# Sheet3.net
KiCad netlist of a schematic drawn in Altium Designer
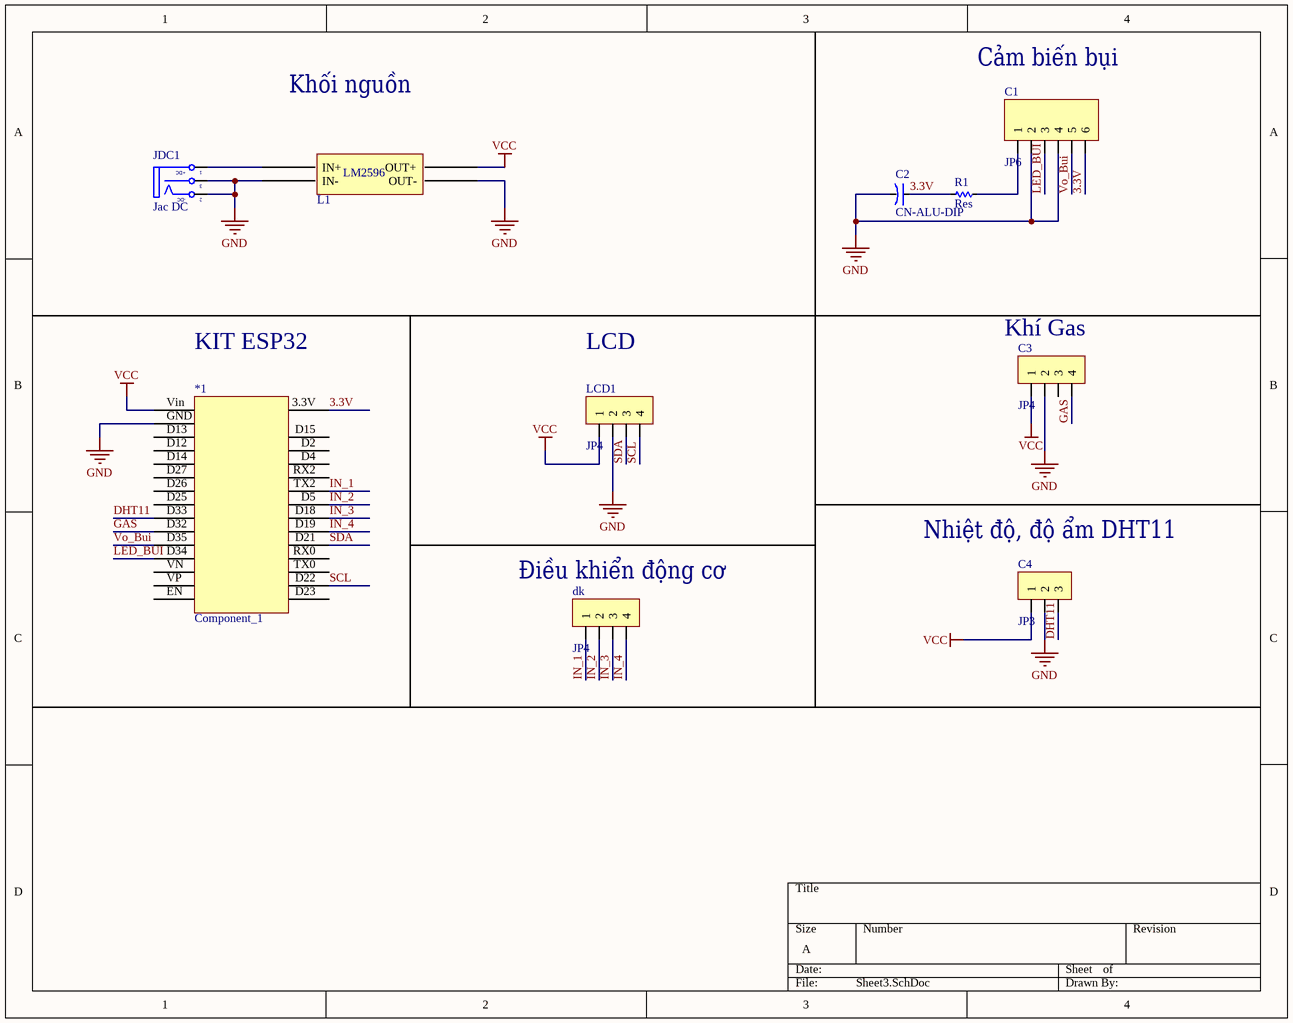
[diagram p0: Sheet3.SchDoc]

(export (version "E")
  (design (tool "Eeschema 10.0.6"))
  (components
    (comp (ref "*1")
      (value "Component_1")
      (footprint "PCBComponent_1")
      (libsource (lib "Schlib1") (part "Component_1"))
    )
    (comp (ref "C1")
      (value "JP6")
      (footprint "JP6-C1T")
      (description "WR-PHD 2.54 mm Angled Socket Header")
      (fields
        (field (name "MANUFACTURER") "Würth Elektronik eiSos GmbH")
        (field (name "PARTNO") "613006143121")
        (field (name "CREATED BY") "Karrer Zheng")
      )
      (libsource (lib "LIBRARY") (part "JP6"))
    )
    (comp (ref "C2")
      (value "CN-ALU-DIP")
      (footprint "CA-ALU-2.54")
      (description "Capacitor (Semiconductor SIM Model)")
      (fields (field (name "PUBLISHER") "Altium Limited"))
      (libsource (lib "LIBRARY") (part "CN-ALU-DIP"))
    )
    (comp (ref "C3")
      (value "JP4")
      (footprint "JP4-C1T")
      (description "WR-PHD 2.54 mm Angled Socket Header")
      (fields
        (field (name "MANUFACTURER") "Würth Elektronik eiSos GmbH")
        (field (name "PARTNO") "613004143121")
        (field (name "CREATED BY") "Karrer Zheng")
      )
      (libsource (lib "LIBRARY") (part "JP4"))
    )
    (comp (ref "C4")
      (value "JP3")
      (footprint "JP3-C1T")
      (description "WR-PHD 2.54 mm Angled Socket Header")
      (fields
        (field (name "MANUFACTURER") "Würth Elektronik eiSos GmbH")
        (field (name "PARTNO") "613003143121")
        (field (name "CREATED BY") "Karrer Zheng")
      )
      (libsource (lib "LIBRARY") (part "JP3"))
    )
    (comp (ref "dk")
      (value "JP4")
      (footprint "JP4-C1T")
      (description "WR-PHD 2.54 mm Angled Socket Header")
      (fields
        (field (name "MANUFACTURER") "Würth Elektronik eiSos GmbH")
        (field (name "PARTNO") "613004143121")
        (field (name "CREATED BY") "Karrer Zheng")
      )
      (libsource (lib "LIBRARY") (part "JP4"))
    )
    (comp (ref "JDC1")
      (value "Jac DC")
      (footprint "DC0")
      (description "Jac DC input")
      (libsource (lib "LIBRARY") (part "DCIN"))
    )
    (comp (ref "L1")
      (value "BUCK_LM2596")
      (footprint "BUCK_LM2596")
      (libsource (lib "BUCK_LM2596_Sch") (part "BUCK_LM2596"))
    )
    (comp (ref "LCD1")
      (value "JP4")
      (footprint "JP4-C1T")
      (description "WR-PHD 2.54 mm Angled Socket Header")
      (fields
        (field (name "MANUFACTURER") "Würth Elektronik eiSos GmbH")
        (field (name "PARTNO") "613004143121")
        (field (name "CREATED BY") "Karrer Zheng")
      )
      (libsource (lib "LIBRARY") (part "JP4"))
    )
    (comp (ref "R1")
      (value "Res")
      (footprint "RES-1/2W")
      (fields
        (field (name "MANUFACTURER") "Generic Components")
        (field (name "PUBLISHER") "Altium Hobart Technology Centre")
      )
      (libsource (lib "LIBRARY") (part "Res"))
    )
  )
  (nets
    (net (code "1") (name "/3.3V") (class "Default")
      (node (ref "C1") (pin "6") (pinfunction "6_6") (pintype "passive"))
      (node (ref "C2") (pin "1") (pinfunction "1_1") (pintype "passive"))
      (node (ref "R1") (pin "1") (pinfunction "1_1") (pintype "passive"))
    )
    (net (code "2") (name "/DHT11") (class "Default")
      (node (ref "C4") (pin "3") (pinfunction "3_3") (pintype "passive"))
    )
    (net (code "3") (name "/GAS") (class "Default")
      (node (ref "C3") (pin "4") (pinfunction "4_4") (pintype "passive"))
    )
    (net (code "4") (name "/IN_1") (class "Default")
      (node (ref "dk") (pin "1") (pinfunction "1_1") (pintype "passive"))
    )
    (net (code "5") (name "/IN_2") (class "Default")
      (node (ref "dk") (pin "2") (pinfunction "2_2") (pintype "passive"))
    )
    (net (code "6") (name "/IN_3") (class "Default")
      (node (ref "dk") (pin "3") (pinfunction "3_3") (pintype "passive"))
    )
    (net (code "7") (name "/IN_4") (class "Default")
      (node (ref "dk") (pin "4") (pinfunction "4_4") (pintype "passive"))
    )
    (net (code "8") (name "/LED_BUI") (class "Default")
      (node (ref "C1") (pin "3") (pinfunction "3_3") (pintype "passive"))
    )
    (net (code "9") (name "/SCL") (class "Default")
      (node (ref "LCD1") (pin "4") (pinfunction "4_4") (pintype "passive"))
    )
    (net (code "10") (name "/SDA") (class "Default")
      (node (ref "LCD1") (pin "3") (pinfunction "3_3") (pintype "passive"))
    )
    (net (code "11") (name "/Vo_Bui") (class "Default")
      (node (ref "C1") (pin "5") (pinfunction "5_5") (pintype "passive"))
    )
    (net (code "12") (name "GND") (class "Default")
      (node (ref "C1") (pin "2") (pinfunction "2_2") (pintype "passive"))
      (node (ref "C1") (pin "4") (pinfunction "4_4") (pintype "passive"))
      (node (ref "C2") (pin "2") (pinfunction "2_2") (pintype "passive"))
      (node (ref "C3") (pin "2") (pinfunction "2_2") (pintype "passive"))
      (node (ref "C4") (pin "2") (pinfunction "2_2") (pintype "passive"))
      (node (ref "JDC1") (pin "2") (pinfunction "TN_2") (pintype "passive"))
      (node (ref "JDC1") (pin "3") (pinfunction "S_3") (pintype "power_in"))
      (node (ref "L1") (pin "2") (pinfunction "IN-_2") (pintype "passive"))
      (node (ref "L1") (pin "3") (pinfunction "OUT-_3") (pintype "passive"))
      (node (ref "LCD1") (pin "2") (pinfunction "2_2") (pintype "passive"))
    )
    (net (code "13") (name "Net-(C1-Pad1)") (class "Default")
      (node (ref "C1") (pin "1") (pinfunction "1_1") (pintype "passive"))
      (node (ref "R1") (pin "2") (pinfunction "2_2") (pintype "passive"))
    )
    (net (code "14") (name "Net-(JDC1-T)") (class "Default")
      (node (ref "JDC1") (pin "1") (pinfunction "T_1") (pintype "passive"))
      (node (ref "L1") (pin "1") (pinfunction "IN+_1") (pintype "passive"))
    )
    (net (code "15") (name "VCC") (class "Default")
      (node (ref "C3") (pin "1") (pinfunction "1_1") (pintype "passive"))
      (node (ref "C4") (pin "1") (pinfunction "1_1") (pintype "passive"))
      (node (ref "L1") (pin "4") (pinfunction "OUT+_4") (pintype "passive"))
      (node (ref "LCD1") (pin "1") (pinfunction "1_1") (pintype "passive"))
    )
    (net (code "16") (name "unconnected-(*1-0-Pad3.3V)") (class "Default")
      (node (ref "*1") (pin "3.3V") (pinfunction "0_3.3V") (pintype "passive"))
    )
    (net (code "17") (name "unconnected-(*1-1-PadGND)") (class "Default")
      (node (ref "*1") (pin "GND") (pinfunction "1_GND") (pintype "passive"))
    )
    (net (code "18") (name "unconnected-(*1-2-PadD15)") (class "Default")
      (node (ref "*1") (pin "D15") (pinfunction "2_D15") (pintype "passive"))
    )
    (net (code "19") (name "unconnected-(*1-3-PadD2)") (class "Default")
      (node (ref "*1") (pin "D2") (pinfunction "3_D2") (pintype "passive"))
    )
    (net (code "20") (name "unconnected-(*1-4-PadD4)") (class "Default")
      (node (ref "*1") (pin "D4") (pinfunction "4_D4") (pintype "passive"))
    )
    (net (code "21") (name "unconnected-(*1-5-PadRX2)") (class "Default")
      (node (ref "*1") (pin "RX2") (pinfunction "5_RX2") (pintype "passive"))
    )
    (net (code "22") (name "unconnected-(*1-6-PadTX2)") (class "Default")
      (node (ref "*1") (pin "TX2") (pinfunction "6_TX2") (pintype "passive"))
    )
    (net (code "23") (name "unconnected-(*1-7-PadD5)") (class "Default")
      (node (ref "*1") (pin "D5") (pinfunction "7_D5") (pintype "passive"))
    )
    (net (code "24") (name "unconnected-(*1-8-PadD18)") (class "Default")
      (node (ref "*1") (pin "D18") (pinfunction "8_D18") (pintype "passive"))
    )
    (net (code "25") (name "unconnected-(*1-9-PadD19)") (class "Default")
      (node (ref "*1") (pin "D19") (pinfunction "9_D19") (pintype "passive"))
    )
    (net (code "26") (name "unconnected-(*1-10-PadD21)") (class "Default")
      (node (ref "*1") (pin "D21") (pinfunction "10_D21") (pintype "passive"))
    )
    (net (code "27") (name "unconnected-(*1-11-PadRX0)") (class "Default")
      (node (ref "*1") (pin "RX0") (pinfunction "11_RX0") (pintype "passive"))
    )
    (net (code "28") (name "unconnected-(*1-12-PadTX0)") (class "Default")
      (node (ref "*1") (pin "TX0") (pinfunction "12_TX0") (pintype "passive"))
    )
    (net (code "29") (name "unconnected-(*1-13-PadD22)") (class "Default")
      (node (ref "*1") (pin "D22") (pinfunction "13_D22") (pintype "passive"))
    )
    (net (code "30") (name "unconnected-(*1-14-PadD23)") (class "Default")
      (node (ref "*1") (pin "D23") (pinfunction "14_D23") (pintype "passive"))
    )
    (net (code "31") (name "unconnected-(*1-15-PadVP)") (class "Default")
      (node (ref "*1") (pin "VP") (pinfunction "15_VP") (pintype "passive"))
    )
    (net (code "32") (name "unconnected-(*1-16-PadEN)") (class "Default")
      (node (ref "*1") (pin "EN") (pinfunction "16_EN") (pintype "passive"))
    )
    (net (code "33") (name "unconnected-(*1-17-PadVN)") (class "Default")
      (node (ref "*1") (pin "VN") (pinfunction "17_VN") (pintype "passive"))
    )
    (net (code "34") (name "unconnected-(*1-18-PadD34)") (class "Default")
      (node (ref "*1") (pin "D34") (pinfunction "18_D34") (pintype "passive"))
    )
    (net (code "35") (name "unconnected-(*1-19-PadD35)") (class "Default")
      (node (ref "*1") (pin "D35") (pinfunction "19_D35") (pintype "passive"))
    )
    (net (code "36") (name "unconnected-(*1-20-PadD32)") (class "Default")
      (node (ref "*1") (pin "D32") (pinfunction "20_D32") (pintype "passive"))
    )
    (net (code "37") (name "unconnected-(*1-21-PadD33)") (class "Default")
      (node (ref "*1") (pin "D33") (pinfunction "21_D33") (pintype "passive"))
    )
    (net (code "38") (name "unconnected-(*1-22-PadD25)") (class "Default")
      (node (ref "*1") (pin "D25") (pinfunction "22_D25") (pintype "passive"))
    )
    (net (code "39") (name "unconnected-(*1-23-PadD26)") (class "Default")
      (node (ref "*1") (pin "D26") (pinfunction "23_D26") (pintype "passive"))
    )
    (net (code "40") (name "unconnected-(*1-24-PadD27)") (class "Default")
      (node (ref "*1") (pin "D27") (pinfunction "24_D27") (pintype "passive"))
    )
    (net (code "41") (name "unconnected-(*1-25-PadD14)") (class "Default")
      (node (ref "*1") (pin "D14") (pinfunction "25_D14") (pintype "passive"))
    )
    (net (code "42") (name "unconnected-(*1-26-PadD12)") (class "Default")
      (node (ref "*1") (pin "D12") (pinfunction "26_D12") (pintype "passive"))
    )
    (net (code "43") (name "unconnected-(*1-27-PadD13)") (class "Default")
      (node (ref "*1") (pin "D13") (pinfunction "27_D13") (pintype "passive"))
    )
    (net (code "44") (name "unconnected-(*1-28-PadGND)") (class "Default")
      (node (ref "*1") (pin "GND") (pinfunction "28_GND") (pintype "passive"))
    )
    (net (code "45") (name "unconnected-(*1-29-PadVin)") (class "Default")
      (node (ref "*1") (pin "Vin") (pinfunction "29_Vin") (pintype "passive"))
    )
    (net (code "46") (name "unconnected-(C3-Pad3)") (class "Default")
      (node (ref "C3") (pin "3") (pinfunction "3_3") (pintype "passive"))
    )
  )
)
